# Sensor_Board.net
KiCad netlist of a schematic drawn in EAGLE
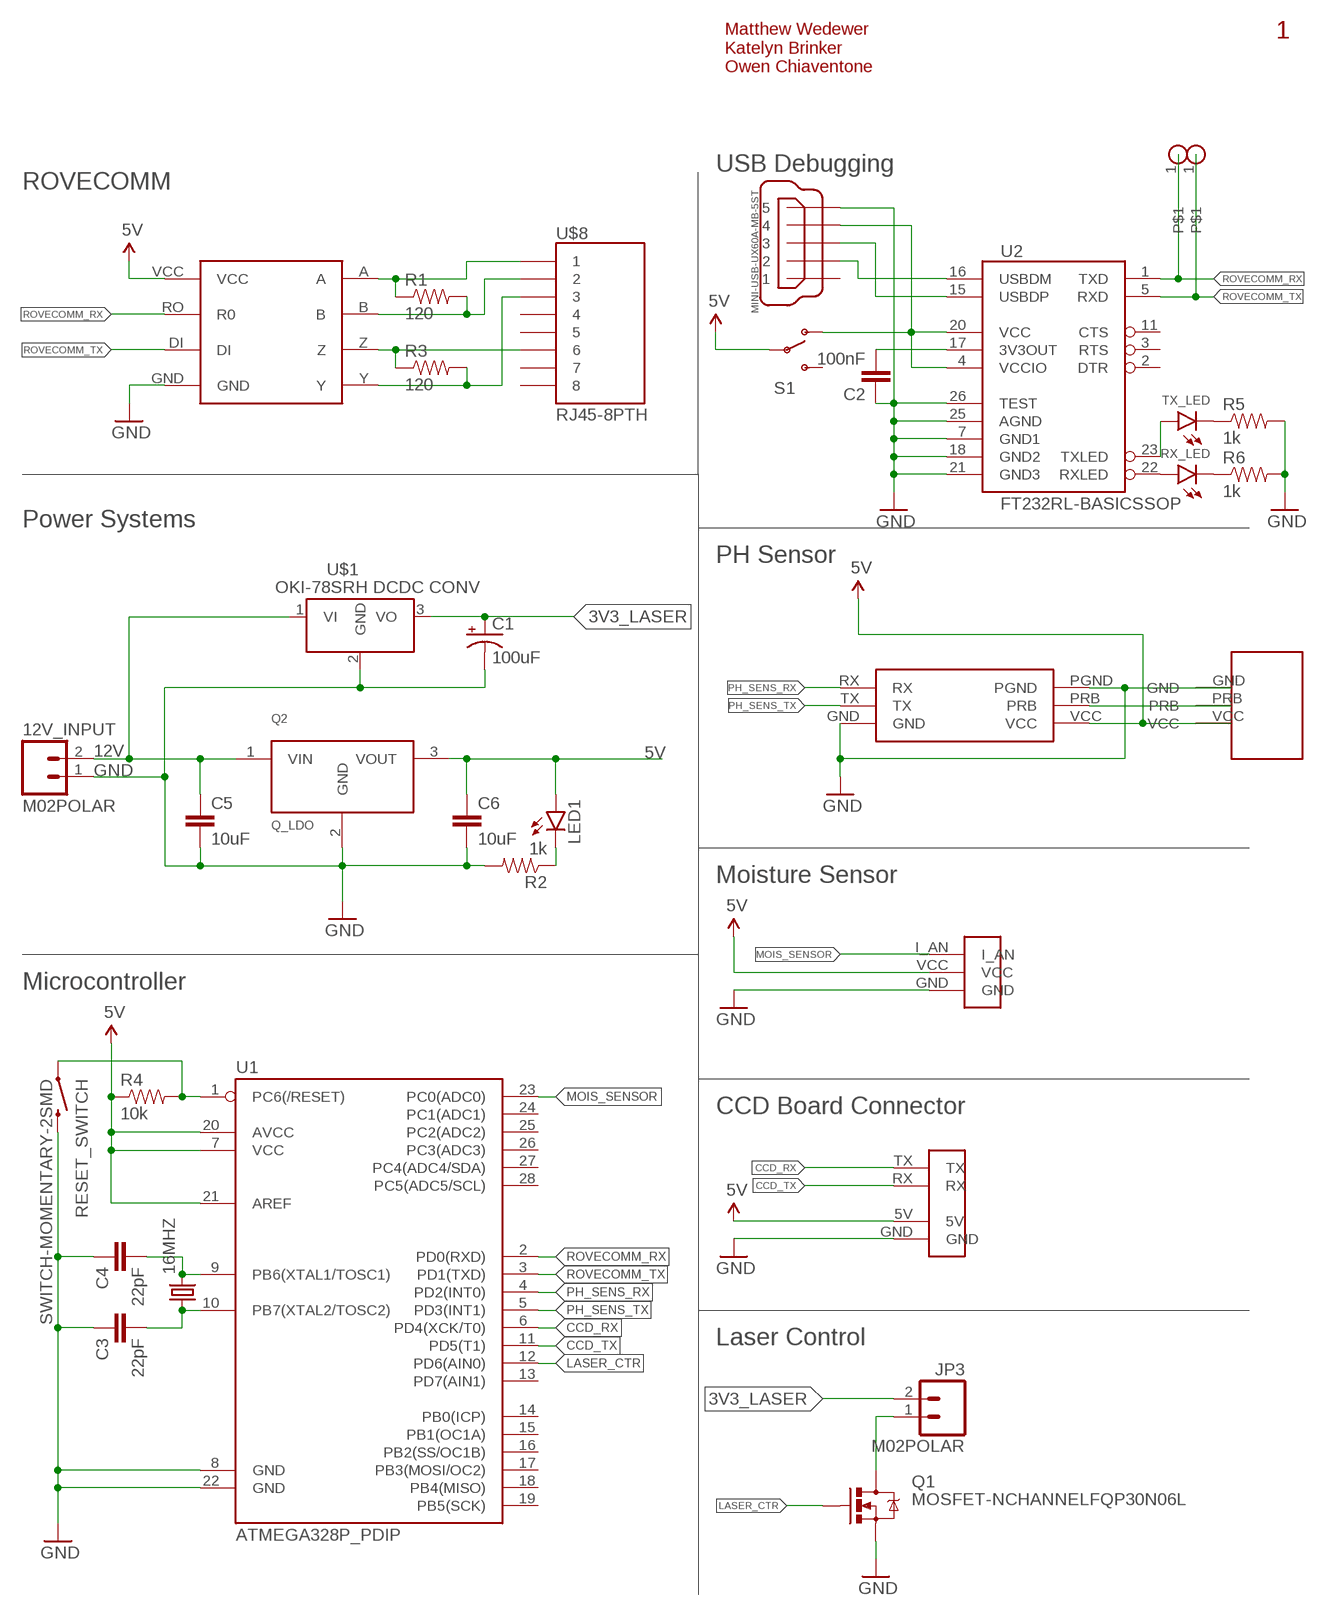
[diagram p0: schematic, sheet 1]

(export (version "E")
  (design (tool "Eeschema 10.0.6"))
  (components
    (comp (ref "12V_INPUT")
      (value "M02POLAR")
      (footprint "eagle-import:MOLEX-1X2")
      (libsource (lib "eagle-import") (part "M02POLAR"))
    )
    (comp (ref "16MHZ")
      (value "CRYSTALHC49US")
      (footprint "eagle-import:HC49US")
      (libsource (lib "eagle-import") (part "CRYSTALHC49US"))
    )
    (comp (ref "C1")
      (value "100uF")
      (footprint "eagle-import:CPOL-RADIAL-100UF-25V")
      (libsource (lib "eagle-import") (part "CAP_POLPTH1"))
    )
    (comp (ref "C2")
      (value "100nF")
      (footprint "eagle-import:1206")
      (libsource (lib "eagle-import") (part "SparkFun-Passives_CAP1206"))
    )
    (comp (ref "C3")
      (value "22pF")
      (footprint "eagle-import:1206")
      (libsource (lib "eagle-import") (part "SparkFun-Passives_CAP1206"))
    )
    (comp (ref "C4")
      (value "22pF")
      (footprint "eagle-import:1206")
      (libsource (lib "eagle-import") (part "SparkFun-Passives_CAP1206"))
    )
    (comp (ref "C5")
      (value "10uF")
      (footprint "eagle-import:1206")
      (libsource (lib "eagle-import") (part "CAP1206"))
    )
    (comp (ref "C6")
      (value "10uF")
      (footprint "eagle-import:1206")
      (libsource (lib "eagle-import") (part "CAP1206"))
    )
    (comp (ref "DEBUG_RX")
      (value "J_HOLE")
      (footprint "eagle-import:J_AWG20")
      (libsource (lib "eagle-import") (part "J_HOLE"))
    )
    (comp (ref "DEBUG_TX")
      (value "J_HOLE")
      (footprint "eagle-import:J_AWG20")
      (libsource (lib "eagle-import") (part "J_HOLE"))
    )
    (comp (ref "JP3")
      (value "M02POLAR")
      (footprint "eagle-import:MOLEX-1X2")
      (libsource (lib "eagle-import") (part "M02POLAR"))
    )
    (comp (ref "LED1")
      (value "LED1206")
      (footprint "eagle-import:LED-1206")
      (libsource (lib "eagle-import") (part "LED1206"))
    )
    (comp (ref "Q1")
      (value "MOSFET-NCHANNELFQP30N06L")
      (footprint "eagle-import:TO220V")
      (libsource (lib "eagle-import") (part "MOSFET-NCHANNELFQP30N06L"))
    )
    (comp (ref "Q2")
      (value "Q_LDO")
      (footprint "eagle-import:TO-220")
      (libsource (lib "eagle-import") (part "Q_LDO"))
    )
    (comp (ref "R1")
      (value "120")
      (footprint "eagle-import:1206")
      (libsource (lib "eagle-import") (part "RESISTOR1206"))
    )
    (comp (ref "R2")
      (value "1k")
      (footprint "eagle-import:1206")
      (libsource (lib "eagle-import") (part "RESISTOR1206"))
    )
    (comp (ref "R3")
      (value "120")
      (footprint "eagle-import:1206")
      (libsource (lib "eagle-import") (part "RESISTOR1206"))
    )
    (comp (ref "R4")
      (value "10k")
      (footprint "eagle-import:1206")
      (libsource (lib "eagle-import") (part "RESISTOR1206"))
    )
    (comp (ref "R5")
      (value "1k")
      (footprint "eagle-import:1206")
      (libsource (lib "eagle-import") (part "RESISTOR1206"))
    )
    (comp (ref "R6")
      (value "1k")
      (footprint "eagle-import:1206")
      (libsource (lib "eagle-import") (part "RESISTOR1206"))
    )
    (comp (ref "RESET_SWITCH")
      (value "SWITCH-MOMENTARY-2SMD")
      (footprint "eagle-import:TACTILE-SWITCH-SMD")
      (libsource (lib "eagle-import") (part "SWITCH-MOMENTARY-2SMD"))
    )
    (comp (ref "RX_LED")
      (value "LED1206")
      (footprint "eagle-import:LED-1206")
      (libsource (lib "eagle-import") (part "LED1206"))
    )
    (comp (ref "S1")
      (value "SWITCH-SPDTPTH")
      (footprint "eagle-import:SWITCH-SPDT")
      (libsource (lib "eagle-import") (part "SWITCH-SPDTPTH"))
    )
    (comp (ref "TX_LED")
      (value "LED1206")
      (footprint "eagle-import:LED-1206")
      (libsource (lib "eagle-import") (part "LED1206"))
    )
    (comp (ref "U$1")
      (value "Q_OKI-78SR")
      (footprint "eagle-import:OKI-78SRH")
      (libsource (lib "eagle-import") (part "Q_OKI-78SR"))
    )
    (comp (ref "U$3")
      (value "PH_EZ0")
      (footprint "eagle-import:PH_EZ0")
      (libsource (lib "eagle-import") (part "PH_EZ0"))
    )
    (comp (ref "U$4")
      (value "PH_CONNECTOR")
      (footprint "eagle-import:PH_CONNECTOR")
      (libsource (lib "eagle-import") (part "PH_CONNECTOR"))
    )
    (comp (ref "U$5")
      (value "MOISTURE_SENSOR")
      (footprint "eagle-import:MOISTURE_SENSOR")
      (libsource (lib "eagle-import") (part "MOISTURE_SENSOR"))
    )
    (comp (ref "U$6")
      (value "CCD_CONNECTOR")
      (footprint "eagle-import:CCD_CONNECTOR")
      (libsource (lib "eagle-import") (part "CCD_CONNECTOR"))
    )
    (comp (ref "U$7")
      (value "MAX3077")
      (footprint "eagle-import:MAX3070E")
      (libsource (lib "eagle-import") (part "MAX3077"))
    )
    (comp (ref "U$8")
      (value "RJ45-8PTH")
      (footprint "eagle-import:RJ45-8")
      (libsource (lib "eagle-import") (part "RJ45-8PTH"))
    )
    (comp (ref "U1")
      (value "ATMEGA328P_PDIP")
      (footprint "eagle-import:DIL28-3")
      (libsource (lib "eagle-import") (part "ATMEGA328P_PDIP"))
    )
    (comp (ref "U2")
      (value "FT232RL-BASICSSOP")
      (footprint "eagle-import:SSOP28DB")
      (libsource (lib "eagle-import") (part "FT232RL-BASICSSOP"))
    )
    (comp (ref "X1")
      (value "MINI-USB-UX60A-MB-5ST")
      (footprint "eagle-import:UX60A-MB-5ST")
      (libsource (lib "eagle-import") (part "MINI-USB-UX60A-MB-5ST"))
    )
  )
  (nets
    (net (code "1") (name "/12V") (class "Default")
      (node (ref "12V_INPUT") (pin "2") (pinfunction "2_2") (pintype "passive"))
      (node (ref "C5") (pin "1") (pinfunction "1_1") (pintype "passive"))
      (node (ref "Q2") (pin "1") (pinfunction "VIN_1") (pintype "bidirectional"))
      (node (ref "U$1") (pin "1") (pinfunction "VI_1") (pintype "bidirectional"))
    )
    (net (code "2") (name "3V3_LASER") (class "Default")
      (node (ref "C1") (pin "1") (pinfunction "+_1") (pintype "passive"))
      (node (ref "JP3") (pin "2") (pinfunction "2_2") (pintype "passive"))
      (node (ref "U$1") (pin "3") (pinfunction "VO_3") (pintype "bidirectional"))
    )
    (net (code "3") (name "5V") (class "Default")
      (node (ref "C6") (pin "1") (pinfunction "1_1") (pintype "passive"))
      (node (ref "LED1") (pin "A") (pinfunction "A_A") (pintype "passive"))
      (node (ref "Q2") (pin "3") (pinfunction "VOUT_3") (pintype "bidirectional"))
      (node (ref "R4") (pin "1") (pinfunction "1_1") (pintype "passive"))
      (node (ref "S1") (pin "2") (pinfunction "P_2") (pintype "passive"))
      (node (ref "U$3") (pin "VCC") (pinfunction "VCC_VCC") (pintype "bidirectional"))
      (node (ref "U$4") (pin "VCC") (pinfunction "VCC_VCC") (pintype "bidirectional"))
      (node (ref "U$5") (pin "VCC") (pinfunction "VCC_VCC") (pintype "bidirectional"))
      (node (ref "U$6") (pin "5V") (pinfunction "5V_5V") (pintype "bidirectional"))
      (node (ref "U$7") (pin "VCC") (pinfunction "VCC_VCC") (pintype "bidirectional"))
      (node (ref "U1") (pin "20") (pinfunction "AVCC_20") (pintype "bidirectional"))
      (node (ref "U1") (pin "21") (pinfunction "AREF_21") (pintype "bidirectional"))
      (node (ref "U1") (pin "7") (pinfunction "VCC_7") (pintype "bidirectional"))
    )
    (net (code "4") (name "CCD_RX") (class "Default")
      (node (ref "U$6") (pin "TX") (pinfunction "TX_TX") (pintype "bidirectional"))
      (node (ref "U1") (pin "6") (pinfunction "PD4(XCK/T0)_6") (pintype "bidirectional"))
    )
    (net (code "5") (name "CCD_TX") (class "Default")
      (node (ref "U$6") (pin "RX") (pinfunction "RX_RX") (pintype "bidirectional"))
      (node (ref "U1") (pin "11") (pinfunction "PD5(T1)_11") (pintype "bidirectional"))
    )
    (net (code "6") (name "GND") (class "Default")
      (node (ref "12V_INPUT") (pin "1") (pinfunction "1_1") (pintype "passive"))
      (node (ref "C1") (pin "2") (pinfunction "-_2") (pintype "passive"))
      (node (ref "C2") (pin "1") (pinfunction "1_1") (pintype "passive"))
      (node (ref "C3") (pin "1") (pinfunction "1_1") (pintype "passive"))
      (node (ref "C4") (pin "1") (pinfunction "1_1") (pintype "passive"))
      (node (ref "C5") (pin "2") (pinfunction "2_2") (pintype "passive"))
      (node (ref "C6") (pin "2") (pinfunction "2_2") (pintype "passive"))
      (node (ref "Q1") (pin "3") (pinfunction "S_3") (pintype "passive"))
      (node (ref "Q2") (pin "2") (pinfunction "GND_2") (pintype "bidirectional"))
      (node (ref "R2") (pin "2") (pinfunction "2_2") (pintype "passive"))
      (node (ref "R5") (pin "2") (pinfunction "2_2") (pintype "passive"))
      (node (ref "R6") (pin "2") (pinfunction "2_2") (pintype "passive"))
      (node (ref "RESET_SWITCH") (pin "3") (pinfunction "2_3") (pintype "passive"))
      (node (ref "U$1") (pin "2") (pinfunction "GND_2") (pintype "bidirectional"))
      (node (ref "U$3") (pin "GND") (pinfunction "GND_GND") (pintype "bidirectional"))
      (node (ref "U$3") (pin "PGND") (pinfunction "PGND_PGND") (pintype "bidirectional"))
      (node (ref "U$4") (pin "GND") (pinfunction "GND_GND") (pintype "bidirectional"))
      (node (ref "U$5") (pin "GND") (pinfunction "GND_GND") (pintype "bidirectional"))
      (node (ref "U$6") (pin "GND") (pinfunction "GND_GND") (pintype "bidirectional"))
      (node (ref "U$7") (pin "GND") (pinfunction "GND_GND") (pintype "bidirectional"))
      (node (ref "U1") (pin "22") (pinfunction "GND_22") (pintype "bidirectional"))
      (node (ref "U1") (pin "8") (pinfunction "GND_8") (pintype "bidirectional"))
      (node (ref "U2") (pin "18") (pinfunction "GND2_18") (pintype "power_in"))
      (node (ref "U2") (pin "21") (pinfunction "GND3_21") (pintype "power_in"))
      (node (ref "U2") (pin "25") (pinfunction "AGND_25") (pintype "power_in"))
      (node (ref "U2") (pin "26") (pinfunction "TEST_26") (pintype "input"))
      (node (ref "U2") (pin "7") (pinfunction "GND1_7") (pintype "power_in"))
      (node (ref "X1") (pin "5") (pinfunction "5_5") (pintype "input"))
    )
    (net (code "7") (name "LASER_CTR") (class "Default")
      (node (ref "Q1") (pin "1") (pinfunction "G_1") (pintype "passive"))
      (node (ref "U1") (pin "12") (pinfunction "PD6(AIN0)_12") (pintype "bidirectional"))
    )
    (net (code "8") (name "MOIS_SENSOR") (class "Default")
      (node (ref "U$5") (pin "I_AN") (pinfunction "I_AN_I_AN") (pintype "bidirectional"))
      (node (ref "U1") (pin "23") (pinfunction "PC0(ADC0)_23") (pintype "bidirectional"))
    )
    (net (code "9") (name "Net-(LED1-PadC)") (class "Default")
      (node (ref "LED1") (pin "C") (pinfunction "C_C") (pintype "passive"))
      (node (ref "R2") (pin "1") (pinfunction "1_1") (pintype "passive"))
    )
    (net (code "10") (name "Net-(Q1-D)") (class "Default")
      (node (ref "JP3") (pin "1") (pinfunction "1_1") (pintype "passive"))
      (node (ref "Q1") (pin "2") (pinfunction "D_2") (pintype "passive"))
    )
    (net (code "11") (name "Net-(R1-Pad1)") (class "Default")
      (node (ref "R1") (pin "1") (pinfunction "1_1") (pintype "passive"))
      (node (ref "U$7") (pin "A") (pinfunction "A_A") (pintype "bidirectional"))
      (node (ref "U$8") (pin "1") (pinfunction "1_1") (pintype "bidirectional"))
    )
    (net (code "12") (name "Net-(R1-Pad2)") (class "Default")
      (node (ref "R1") (pin "2") (pinfunction "2_2") (pintype "passive"))
      (node (ref "U$7") (pin "B") (pinfunction "B_B") (pintype "bidirectional"))
      (node (ref "U$8") (pin "2") (pinfunction "2_2") (pintype "bidirectional"))
    )
    (net (code "13") (name "Net-(R3-Pad1)") (class "Default")
      (node (ref "R3") (pin "1") (pinfunction "1_1") (pintype "passive"))
      (node (ref "U$7") (pin "Z") (pinfunction "Z_Z") (pintype "bidirectional"))
      (node (ref "U$8") (pin "6") (pinfunction "6_6") (pintype "bidirectional"))
    )
    (net (code "14") (name "Net-(R3-Pad2)") (class "Default")
      (node (ref "R3") (pin "2") (pinfunction "2_2") (pintype "passive"))
      (node (ref "U$7") (pin "Y") (pinfunction "Y_Y") (pintype "bidirectional"))
      (node (ref "U$8") (pin "3") (pinfunction "3_3") (pintype "bidirectional"))
    )
    (net (code "15") (name "Net-(R5-Pad1)") (class "Default")
      (node (ref "R5") (pin "1") (pinfunction "1_1") (pintype "passive"))
      (node (ref "TX_LED") (pin "C") (pinfunction "C_C") (pintype "passive"))
    )
    (net (code "16") (name "Net-(R6-Pad1)") (class "Default")
      (node (ref "R6") (pin "1") (pinfunction "1_1") (pintype "passive"))
      (node (ref "RX_LED") (pin "C") (pinfunction "C_C") (pintype "passive"))
    )
    (net (code "17") (name "Net-(S1-O)") (class "Default")
      (node (ref "S1") (pin "1") (pinfunction "O_1") (pintype "passive"))
      (node (ref "U2") (pin "20") (pinfunction "VCC_20") (pintype "power_in"))
      (node (ref "U2") (pin "4") (pinfunction "VCCIO_4") (pintype "power_in"))
      (node (ref "X1") (pin "4") (pinfunction "4_4") (pintype "input"))
    )
    (net (code "18") (name "Net-(U$3-PadPRB)") (class "Default")
      (node (ref "U$3") (pin "PRB") (pinfunction "PRB_PRB") (pintype "bidirectional"))
      (node (ref "U$4") (pin "PRB") (pinfunction "PRB_PRB") (pintype "bidirectional"))
    )
    (net (code "19") (name "Net-(U1-PB6(XTAL1{slash}TOSC1))") (class "Default")
      (node (ref "16MHZ") (pin "2") (pinfunction "2_2") (pintype "passive"))
      (node (ref "C4") (pin "2") (pinfunction "2_2") (pintype "passive"))
      (node (ref "U1") (pin "9") (pinfunction "PB6(XTAL1/TOSC1)_9") (pintype "bidirectional"))
    )
    (net (code "20") (name "Net-(U1-PB7(XTAL2{slash}TOSC2))") (class "Default")
      (node (ref "16MHZ") (pin "1") (pinfunction "1_1") (pintype "passive"))
      (node (ref "C3") (pin "2") (pinfunction "2_2") (pintype "passive"))
      (node (ref "U1") (pin "10") (pinfunction "PB7(XTAL2/TOSC2)_10") (pintype "bidirectional"))
    )
    (net (code "21") (name "Net-(U1-PC6({slash}RESET))") (class "Default")
      (node (ref "R4") (pin "2") (pinfunction "2_2") (pintype "passive"))
      (node (ref "RESET_SWITCH") (pin "1") (pinfunction "1_1") (pintype "passive"))
      (node (ref "U1") (pin "1") (pinfunction "PC6(/RESET)_1") (pintype "bidirectional"))
    )
    (net (code "22") (name "Net-(U2-3V3OUT)") (class "Default")
      (node (ref "C2") (pin "2") (pinfunction "2_2") (pintype "passive"))
      (node (ref "U2") (pin "17") (pinfunction "3V3OUT_17") (pintype "output"))
    )
    (net (code "23") (name "Net-(U2-RXLED)") (class "Default")
      (node (ref "RX_LED") (pin "A") (pinfunction "A_A") (pintype "passive"))
      (node (ref "U2") (pin "22") (pinfunction "RXLED_22") (pintype "bidirectional"))
    )
    (net (code "24") (name "Net-(U2-TXLED)") (class "Default")
      (node (ref "TX_LED") (pin "A") (pinfunction "A_A") (pintype "passive"))
      (node (ref "U2") (pin "23") (pinfunction "TXLED_23") (pintype "bidirectional"))
    )
    (net (code "25") (name "Net-(U2-USBDM)") (class "Default")
      (node (ref "U2") (pin "16") (pinfunction "USBDM_16") (pintype "bidirectional"))
      (node (ref "X1") (pin "2") (pinfunction "2_2") (pintype "input"))
    )
    (net (code "26") (name "Net-(U2-USBDP)") (class "Default")
      (node (ref "U2") (pin "15") (pinfunction "USBDP_15") (pintype "bidirectional"))
      (node (ref "X1") (pin "3") (pinfunction "3_3") (pintype "input"))
    )
    (net (code "27") (name "PH_SENS_RX") (class "Default")
      (node (ref "U$3") (pin "RX") (pinfunction "RX_RX") (pintype "bidirectional"))
      (node (ref "U1") (pin "4") (pinfunction "PD2(INT0)_4") (pintype "bidirectional"))
    )
    (net (code "28") (name "PH_SENS_TX") (class "Default")
      (node (ref "U$3") (pin "TX") (pinfunction "TX_TX") (pintype "bidirectional"))
      (node (ref "U1") (pin "5") (pinfunction "PD3(INT1)_5") (pintype "bidirectional"))
    )
    (net (code "29") (name "ROVECOMM_RX") (class "Default")
      (node (ref "DEBUG_RX") (pin "1") (pinfunction "P$1_1") (pintype "bidirectional"))
      (node (ref "U$7") (pin "RO") (pinfunction "R0_RO") (pintype "bidirectional"))
      (node (ref "U1") (pin "2") (pinfunction "PD0(RXD)_2") (pintype "bidirectional"))
      (node (ref "U2") (pin "1") (pinfunction "TXD_1") (pintype "output"))
    )
    (net (code "30") (name "ROVECOMM_TX") (class "Default")
      (node (ref "DEBUG_TX") (pin "1") (pinfunction "P$1_1") (pintype "bidirectional"))
      (node (ref "U$7") (pin "DI") (pinfunction "DI_DI") (pintype "bidirectional"))
      (node (ref "U1") (pin "3") (pinfunction "PD1(TXD)_3") (pintype "bidirectional"))
      (node (ref "U2") (pin "5") (pinfunction "RXD_5") (pintype "input"))
    )
    (net (code "31") (name "unconnected-(S1-S-Pad3)") (class "Default")
      (node (ref "S1") (pin "3") (pinfunction "S_3") (pintype "passive"))
    )
    (net (code "32") (name "unconnected-(U$8-Pad4)") (class "Default")
      (node (ref "U$8") (pin "4") (pinfunction "4_4") (pintype "bidirectional"))
    )
    (net (code "33") (name "unconnected-(U$8-Pad5)") (class "Default")
      (node (ref "U$8") (pin "5") (pinfunction "5_5") (pintype "bidirectional"))
    )
    (net (code "34") (name "unconnected-(U$8-Pad7)") (class "Default")
      (node (ref "U$8") (pin "7") (pinfunction "7_7") (pintype "bidirectional"))
    )
    (net (code "35") (name "unconnected-(U$8-Pad8)") (class "Default")
      (node (ref "U$8") (pin "8") (pinfunction "8_8") (pintype "bidirectional"))
    )
    (net (code "36") (name "unconnected-(U1-PB0(ICP)-Pad14)") (class "Default")
      (node (ref "U1") (pin "14") (pinfunction "PB0(ICP)_14") (pintype "bidirectional"))
    )
    (net (code "37") (name "unconnected-(U1-PB1(OC1A)-Pad15)") (class "Default")
      (node (ref "U1") (pin "15") (pinfunction "PB1(OC1A)_15") (pintype "bidirectional"))
    )
    (net (code "38") (name "unconnected-(U1-PB2(SS{slash}OC1B)-Pad16)") (class "Default")
      (node (ref "U1") (pin "16") (pinfunction "PB2(SS/OC1B)_16") (pintype "bidirectional"))
    )
    (net (code "39") (name "unconnected-(U1-PB3(MOSI{slash}OC2)-Pad17)") (class "Default")
      (node (ref "U1") (pin "17") (pinfunction "PB3(MOSI/OC2)_17") (pintype "bidirectional"))
    )
    (net (code "40") (name "unconnected-(U1-PB4(MISO)-Pad18)") (class "Default")
      (node (ref "U1") (pin "18") (pinfunction "PB4(MISO)_18") (pintype "bidirectional"))
    )
    (net (code "41") (name "unconnected-(U1-PB5(SCK)-Pad19)") (class "Default")
      (node (ref "U1") (pin "19") (pinfunction "PB5(SCK)_19") (pintype "bidirectional"))
    )
    (net (code "42") (name "unconnected-(U1-PC1(ADC1)-Pad24)") (class "Default")
      (node (ref "U1") (pin "24") (pinfunction "PC1(ADC1)_24") (pintype "bidirectional"))
    )
    (net (code "43") (name "unconnected-(U1-PC2(ADC2)-Pad25)") (class "Default")
      (node (ref "U1") (pin "25") (pinfunction "PC2(ADC2)_25") (pintype "bidirectional"))
    )
    (net (code "44") (name "unconnected-(U1-PC3(ADC3)-Pad26)") (class "Default")
      (node (ref "U1") (pin "26") (pinfunction "PC3(ADC3)_26") (pintype "bidirectional"))
    )
    (net (code "45") (name "unconnected-(U1-PC4(ADC4{slash}SDA)-Pad27)") (class "Default")
      (node (ref "U1") (pin "27") (pinfunction "PC4(ADC4/SDA)_27") (pintype "bidirectional"))
    )
    (net (code "46") (name "unconnected-(U1-PC5(ADC5{slash}SCL)-Pad28)") (class "Default")
      (node (ref "U1") (pin "28") (pinfunction "PC5(ADC5/SCL)_28") (pintype "bidirectional"))
    )
    (net (code "47") (name "unconnected-(U1-PD7(AIN1)-Pad13)") (class "Default")
      (node (ref "U1") (pin "13") (pinfunction "PD7(AIN1)_13") (pintype "bidirectional"))
    )
    (net (code "48") (name "unconnected-(U2-CTS-Pad11)") (class "Default")
      (node (ref "U2") (pin "11") (pinfunction "CTS_11") (pintype "bidirectional"))
    )
    (net (code "49") (name "unconnected-(U2-DTR-Pad2)") (class "Default")
      (node (ref "U2") (pin "2") (pinfunction "DTR_2") (pintype "bidirectional"))
    )
    (net (code "50") (name "unconnected-(U2-RTS-Pad3)") (class "Default")
      (node (ref "U2") (pin "3") (pinfunction "RTS_3") (pintype "bidirectional"))
    )
    (net (code "51") (name "unconnected-(X1-Pad1)") (class "Default")
      (node (ref "X1") (pin "1") (pinfunction "1_1") (pintype "input"))
    )
  )
)
